# design.net
KiCad netlist of a schematic drawn in Altium Designer
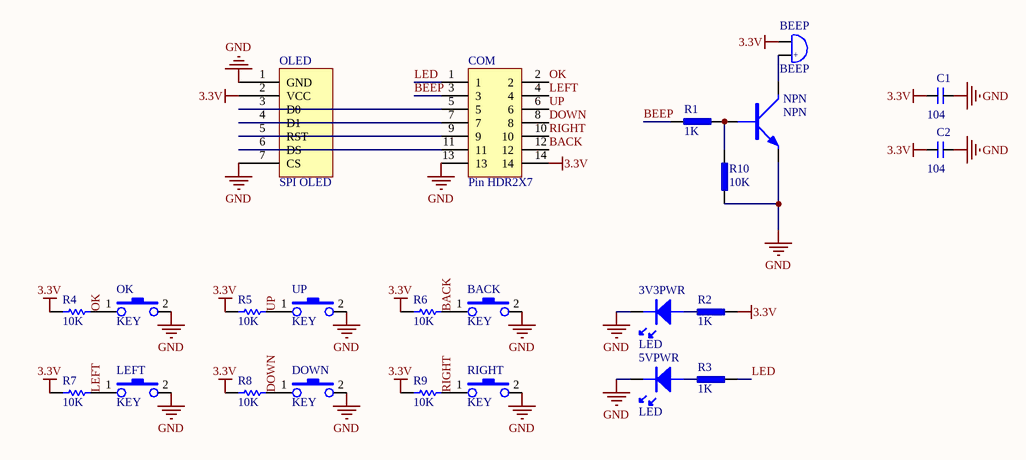
[diagram p0: 菜单顶板.SchDoc]

(export (version "E")
  (design (tool "Eeschema 10.0.6"))
  (components
    (comp (ref "3V3PWR") (value "LED") (footprint "LED-0805B") (libsource (lib "LED") (part "LED")))
    (comp (ref "5VPWR") (value "LED") (footprint "LED-0805B") (libsource (lib "LED") (part "LED")))
    (comp (ref "BACK") (value "KEY") (footprint "anjian") (libsource (lib "轻触开关") (part "KEY")))
    (comp (ref "BEEP")
      (value "BEEP")
      (footprint "BEEP 6.5x12x6")
      (description "蜂鸣器")
      (libsource (lib "蜂鸣器") (part "BEEP"))
    )
    (comp (ref "C1") (value "104") (footprint "C 0805") (libsource (lib "常用原理图库") (part "CAP")))
    (comp (ref "C2") (value "104") (footprint "C 0805") (libsource (lib "常用原理图库") (part "CAP")))
    (comp (ref "COM")
      (value "Pin HDR2X7")
      (footprint "Pin HDR2X7/2.54mm-S")
      (libsource (lib "排针") (part "Pin HDR2X7"))
    )
    (comp (ref "DOWN") (value "KEY") (footprint "anjian") (libsource (lib "轻触开关") (part "KEY")))
    (comp (ref "LEFT") (value "KEY") (footprint "anjian") (libsource (lib "轻触开关") (part "KEY")))
    (comp (ref "NPN")
      (value "NPN")
      (footprint "SOT-23")
      (description "NPN三极管")
      (libsource (lib "三极管") (part "NPN"))
    )
    (comp (ref "OK") (value "KEY") (footprint "anjian") (libsource (lib "轻触开关") (part "KEY")))
    (comp (ref "OLED")
      (value "SPI OLED")
      (footprint "OLED12864")
      (libsource (lib "常用原理图库") (part "SPI OLED"))
    )
    (comp (ref "R1") (value "1K") (footprint "R 0805") (libsource (lib "常用原理图库") (part "RES")))
    (comp (ref "R2") (value "1K") (footprint "R 0805") (libsource (lib "") (part "RES_2")))
    (comp (ref "R3") (value "1K") (footprint "R 0805") (libsource (lib "") (part "RES_2")))
    (comp (ref "R4") (value "10K") (footprint "0805R") (libsource (lib "电阻") (part "RES")))
    (comp (ref "R5") (value "10K") (footprint "0805R") (libsource (lib "电阻") (part "RES")))
    (comp (ref "R6") (value "10K") (footprint "0805R") (libsource (lib "电阻") (part "RES")))
    (comp (ref "R7") (value "10K") (footprint "0805R") (libsource (lib "电阻") (part "RES")))
    (comp (ref "R8") (value "10K") (footprint "0805R") (libsource (lib "电阻") (part "RES")))
    (comp (ref "R9") (value "10K") (footprint "0805R") (libsource (lib "电阻") (part "RES")))
    (comp (ref "R10") (value "10K") (footprint "R 0805") (libsource (lib "") (part "RES_1")))
    (comp (ref "RIGHT") (value "KEY") (footprint "anjian") (libsource (lib "轻触开关") (part "KEY")))
    (comp (ref "UP") (value "KEY") (footprint "anjian") (libsource (lib "轻触开关") (part "KEY")))
  )
  (nets
    (net (code "1") (name "/BACK") (class "Default")
      (node (ref "BACK") (pin "1") (pinfunction "1_1") (pintype "passive"))
      (node (ref "COM") (pin "12") (pinfunction "12_12") (pintype "passive"))
      (node (ref "R6") (pin "2") (pinfunction "2_2") (pintype "passive"))
    )
    (net (code "2") (name "/BEEP") (class "Default")
      (node (ref "COM") (pin "3") (pinfunction "3_3") (pintype "passive"))
      (node (ref "R1") (pin "1") (pintype "passive"))
    )
    (net (code "3") (name "/DOWN") (class "Default")
      (node (ref "COM") (pin "8") (pinfunction "8_8") (pintype "passive"))
      (node (ref "DOWN") (pin "1") (pinfunction "1_1") (pintype "passive"))
      (node (ref "R8") (pin "2") (pinfunction "2_2") (pintype "passive"))
    )
    (net (code "4") (name "/LED") (class "Default")
      (node (ref "COM") (pin "1") (pinfunction "1_1") (pintype "passive"))
      (node (ref "R3") (pin "1") (pintype "passive"))
    )
    (net (code "5") (name "/LEFT") (class "Default")
      (node (ref "COM") (pin "4") (pinfunction "4_4") (pintype "passive"))
      (node (ref "LEFT") (pin "1") (pinfunction "1_1") (pintype "passive"))
      (node (ref "R7") (pin "2") (pinfunction "2_2") (pintype "passive"))
    )
    (net (code "6") (name "/OK") (class "Default")
      (node (ref "COM") (pin "2") (pinfunction "2_2") (pintype "passive"))
      (node (ref "OK") (pin "1") (pinfunction "1_1") (pintype "passive"))
      (node (ref "R4") (pin "2") (pinfunction "2_2") (pintype "passive"))
    )
    (net (code "7") (name "/RIGHT") (class "Default")
      (node (ref "COM") (pin "10") (pinfunction "10_10") (pintype "passive"))
      (node (ref "R9") (pin "2") (pinfunction "2_2") (pintype "passive"))
      (node (ref "RIGHT") (pin "1") (pinfunction "1_1") (pintype "passive"))
    )
    (net (code "8") (name "/UP") (class "Default")
      (node (ref "COM") (pin "6") (pinfunction "6_6") (pintype "passive"))
      (node (ref "R5") (pin "2") (pinfunction "2_2") (pintype "passive"))
      (node (ref "UP") (pin "1") (pinfunction "1_1") (pintype "passive"))
    )
    (net (code "9") (name "3.3V") (class "Default")
      (node (ref "BEEP") (pin "2") (pinfunction "2_2") (pintype "passive"))
      (node (ref "C1") (pin "1") (pintype "passive"))
      (node (ref "C2") (pin "1") (pintype "passive"))
      (node (ref "COM") (pin "14") (pinfunction "14_14") (pintype "passive"))
      (node (ref "OLED") (pin "2") (pinfunction "VCC_2") (pintype "passive"))
      (node (ref "R2") (pin "1") (pintype "passive"))
      (node (ref "R4") (pin "1") (pinfunction "1_1") (pintype "passive"))
      (node (ref "R5") (pin "1") (pinfunction "1_1") (pintype "passive"))
      (node (ref "R6") (pin "1") (pinfunction "1_1") (pintype "passive"))
      (node (ref "R7") (pin "1") (pinfunction "1_1") (pintype "passive"))
      (node (ref "R8") (pin "1") (pinfunction "1_1") (pintype "passive"))
      (node (ref "R9") (pin "1") (pinfunction "1_1") (pintype "passive"))
    )
    (net (code "10") (name "GND") (class "Default")
      (node (ref "3V3PWR") (pin "K") (pinfunction "K_K") (pintype "passive"))
      (node (ref "5VPWR") (pin "K") (pinfunction "K_K") (pintype "passive"))
      (node (ref "BACK") (pin "2") (pinfunction "2_2") (pintype "passive"))
      (node (ref "C1") (pin "2") (pintype "passive"))
      (node (ref "C2") (pin "2") (pintype "passive"))
      (node (ref "COM") (pin "13") (pinfunction "13_13") (pintype "passive"))
      (node (ref "DOWN") (pin "2") (pinfunction "2_2") (pintype "passive"))
      (node (ref "LEFT") (pin "2") (pinfunction "2_2") (pintype "passive"))
      (node (ref "NPN") (pin "E") (pinfunction "E_E") (pintype "passive"))
      (node (ref "OK") (pin "2") (pinfunction "2_2") (pintype "passive"))
      (node (ref "OLED") (pin "1") (pinfunction "GND_1") (pintype "passive"))
      (node (ref "OLED") (pin "7") (pinfunction "CS_7") (pintype "passive"))
      (node (ref "R10") (pin "1") (pintype "passive"))
      (node (ref "RIGHT") (pin "2") (pinfunction "2_2") (pintype "passive"))
      (node (ref "UP") (pin "2") (pinfunction "2_2") (pintype "passive"))
    )
    (net (code "11") (name "Net-(3V3PWR-PadA)") (class "Default")
      (node (ref "3V3PWR") (pin "A") (pinfunction "A_A") (pintype "passive"))
      (node (ref "R2") (pin "2") (pintype "passive"))
    )
    (net (code "12") (name "Net-(5VPWR-PadA)") (class "Default")
      (node (ref "5VPWR") (pin "A") (pinfunction "A_A") (pintype "passive"))
      (node (ref "R3") (pin "2") (pintype "passive"))
    )
    (net (code "13") (name "Net-(BEEP-Pad1)") (class "Default")
      (node (ref "BEEP") (pin "1") (pinfunction "1_1") (pintype "passive"))
      (node (ref "NPN") (pin "C") (pinfunction "C_C") (pintype "passive"))
    )
    (net (code "14") (name "Net-(NPN-PadB)") (class "Default")
      (node (ref "NPN") (pin "B") (pinfunction "B_B") (pintype "passive"))
      (node (ref "R1") (pin "2") (pintype "passive"))
      (node (ref "R10") (pin "2") (pintype "passive"))
    )
    (net (code "15") (name "Net-(OLED-D0)") (class "Default")
      (node (ref "COM") (pin "5") (pinfunction "5_5") (pintype "passive"))
      (node (ref "OLED") (pin "3") (pinfunction "D0_3") (pintype "passive"))
    )
    (net (code "16") (name "Net-(OLED-D1)") (class "Default")
      (node (ref "COM") (pin "7") (pinfunction "7_7") (pintype "passive"))
      (node (ref "OLED") (pin "4") (pinfunction "D1_4") (pintype "passive"))
    )
    (net (code "17") (name "Net-(OLED-DS)") (class "Default")
      (node (ref "COM") (pin "11") (pinfunction "11_11") (pintype "passive"))
      (node (ref "OLED") (pin "6") (pinfunction "DS_6") (pintype "passive"))
    )
    (net (code "18") (name "Net-(OLED-RST)") (class "Default")
      (node (ref "COM") (pin "9") (pinfunction "9_9") (pintype "passive"))
      (node (ref "OLED") (pin "5") (pinfunction "RST_5") (pintype "passive"))
    )
  )
)
